# starterkit_v2.net
KiCad netlist of a schematic drawn in EAGLE
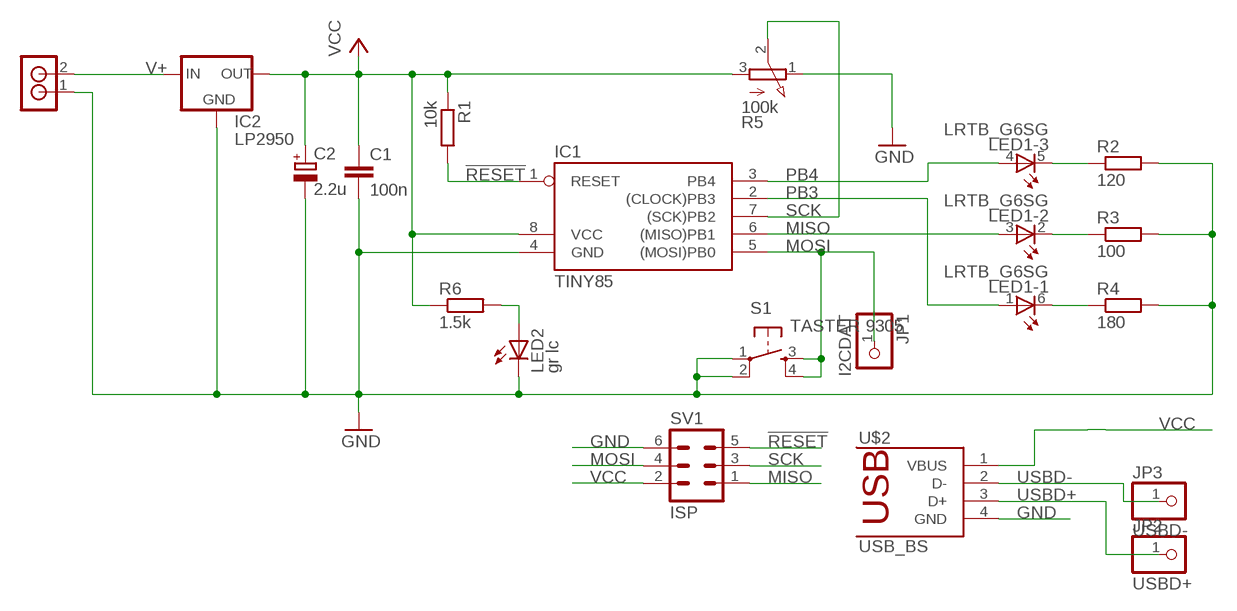
[diagram p0: schematic, sheet 1]

(export (version "E")
  (design (tool "Eeschema 10.0.6"))
  (components
    (comp (ref "C1")
      (value "100n")
      (footprint "eagle-import:C0805")
      (libsource (lib "eagle-import") (part "C-EUC0805"))
    )
    (comp (ref "C2")
      (value "2.2u")
      (footprint "eagle-import:E2-5")
      (libsource (lib "eagle-import") (part "CPOL-EUE2-5"))
    )
    (comp (ref "IC1")
      (value "TINY85")
      (footprint "eagle-import:DIL08")
      (libsource (lib "eagle-import") (part "TINY22P"))
    )
    (comp (ref "IC2")
      (value "LP2950")
      (footprint "eagle-import:TO92")
      (libsource (lib "eagle-import") (part "LP2950?ACZ-5.0"))
    )
    (comp (ref "JP1")
      (value "I2CDAT")
      (footprint "eagle-import:1X01")
      (libsource (lib "eagle-import") (part "PINHD-1X1"))
    )
    (comp (ref "JP2")
      (value "USBD+")
      (footprint "eagle-import:1X01")
      (libsource (lib "eagle-import") (part "PINHD-1X1"))
    )
    (comp (ref "JP3")
      (value "USBD-")
      (footprint "eagle-import:1X01")
      (libsource (lib "eagle-import") (part "PINHD-1X1"))
    )
    (comp (ref "LED1")
      (value "LRTB_G6SG")
      (footprint "eagle-import:LRTB_G6SG")
      (libsource (lib "eagle-import") (part "LRTB_G6SG"))
    )
    (comp (ref "LED2")
      (value "gr lc")
      (footprint "eagle-import:LED3MM")
      (libsource (lib "eagle-import") (part "LED3MM"))
    )
    (comp (ref "R1")
      (value "10k")
      (footprint "eagle-import:R0805")
      (libsource (lib "eagle-import") (part "R-EU_R0805"))
    )
    (comp (ref "R2")
      (value "120")
      (footprint "eagle-import:R0805")
      (libsource (lib "eagle-import") (part "R-EU_R0805"))
    )
    (comp (ref "R3")
      (value "100")
      (footprint "eagle-import:R0805")
      (libsource (lib "eagle-import") (part "R-EU_R0805"))
    )
    (comp (ref "R4")
      (value "180")
      (footprint "eagle-import:R0805")
      (libsource (lib "eagle-import") (part "R-EU_R0805"))
    )
    (comp (ref "R5")
      (value "100k")
      (footprint "eagle-import:ALPS_RK09K113")
      (libsource (lib "eagle-import") (part "ALPS_RK09K113"))
    )
    (comp (ref "R6")
      (value "1.5k")
      (footprint "eagle-import:R0805")
      (libsource (lib "eagle-import") (part "R-EU_R0805"))
    )
    (comp (ref "S1")
      (value "TASTER 9305")
      (footprint "eagle-import:JTP-1130")
      (libsource (lib "eagle-import") (part "JTP-1130C"))
    )
    (comp (ref "SV1")
      (value "ISP")
      (footprint "eagle-import:ML6")
      (libsource (lib "eagle-import") (part "ML6"))
    )
    (comp (ref "U$1")
      (value "RIACON_101_2")
      (footprint "eagle-import:RIACON_101_2")
      (libsource (lib "eagle-import") (part "RIACON_101_2"))
    )
    (comp (ref "U$2")
      (value "USB_BS")
      (footprint "eagle-import:USB_B_UP-S")
      (libsource (lib "eagle-import") (part "USB_BS"))
    )
  )
  (nets
    (net (code "1") (name "/MISO") (class "Default")
      (node (ref "IC1") (pin "6") (pinfunction "(MISO)PB1_6") (pintype "bidirectional"))
      (node (ref "LED1") (pin "3") (pinfunction "A_3") (pintype "passive"))
      (node (ref "SV1") (pin "1") (pinfunction "1_1") (pintype "passive"))
    )
    (net (code "2") (name "/MOSI") (class "Default")
      (node (ref "IC1") (pin "5") (pinfunction "(MOSI)PB0_5") (pintype "bidirectional"))
      (node (ref "JP1") (pin "1") (pinfunction "1_1") (pintype "passive"))
      (node (ref "S1") (pin "3") (pinfunction "S_3") (pintype "passive"))
      (node (ref "S1") (pin "4") (pinfunction "S1_4") (pintype "passive"))
      (node (ref "SV1") (pin "4") (pinfunction "4_4") (pintype "passive"))
    )
    (net (code "3") (name "/PB3") (class "Default")
      (node (ref "IC1") (pin "2") (pinfunction "(CLOCK)PB3_2") (pintype "bidirectional"))
      (node (ref "LED1") (pin "1") (pinfunction "A_1") (pintype "passive"))
    )
    (net (code "4") (name "/PB4") (class "Default")
      (node (ref "IC1") (pin "3") (pinfunction "PB4_3") (pintype "bidirectional"))
      (node (ref "LED1") (pin "4") (pinfunction "A_4") (pintype "passive"))
    )
    (net (code "5") (name "/SCK") (class "Default")
      (node (ref "IC1") (pin "7") (pinfunction "(SCK)PB2_7") (pintype "bidirectional"))
      (node (ref "R5") (pin "2") (pinfunction "S_2") (pintype "passive"))
      (node (ref "SV1") (pin "3") (pinfunction "3_3") (pintype "passive"))
    )
    (net (code "6") (name "/USBD+") (class "Default")
      (node (ref "JP2") (pin "1") (pinfunction "1_1") (pintype "passive"))
      (node (ref "U$2") (pin "3") (pinfunction "D+_3") (pintype "passive"))
    )
    (net (code "7") (name "/USBD-") (class "Default")
      (node (ref "JP3") (pin "1") (pinfunction "1_1") (pintype "passive"))
      (node (ref "U$2") (pin "2") (pinfunction "D-_2") (pintype "passive"))
    )
    (net (code "8") (name "/V+") (class "Default")
      (node (ref "IC2") (pin "3") (pinfunction "IN_3") (pintype "input"))
      (node (ref "U$1") (pin "2") (pinfunction "2_2") (pintype "passive"))
    )
    (net (code "9") (name "/~{RESET}") (class "Default")
      (node (ref "IC1") (pin "1") (pinfunction "RESET_1") (pintype "input"))
      (node (ref "R1") (pin "2") (pinfunction "2_2") (pintype "passive"))
      (node (ref "SV1") (pin "5") (pinfunction "5_5") (pintype "passive"))
    )
    (net (code "10") (name "GND") (class "Default")
      (node (ref "C1") (pin "2") (pinfunction "2_2") (pintype "passive"))
      (node (ref "C2") (pin "-") (pinfunction "-_-") (pintype "passive"))
      (node (ref "IC1") (pin "4") (pinfunction "GND_4") (pintype "power_in"))
      (node (ref "IC2") (pin "2") (pinfunction "GND_2") (pintype "input"))
      (node (ref "LED2") (pin "K") (pinfunction "C_K") (pintype "passive"))
      (node (ref "R2") (pin "2") (pinfunction "2_2") (pintype "passive"))
      (node (ref "R3") (pin "2") (pinfunction "2_2") (pintype "passive"))
      (node (ref "R4") (pin "2") (pinfunction "2_2") (pintype "passive"))
      (node (ref "R5") (pin "1") (pinfunction "E_1") (pintype "passive"))
      (node (ref "S1") (pin "1") (pinfunction "P_1") (pintype "passive"))
      (node (ref "S1") (pin "2") (pinfunction "P1_2") (pintype "passive"))
      (node (ref "SV1") (pin "6") (pinfunction "6_6") (pintype "passive"))
      (node (ref "U$1") (pin "1") (pinfunction "1_1") (pintype "passive"))
      (node (ref "U$2") (pin "4") (pinfunction "GND_4") (pintype "passive"))
    )
    (net (code "11") (name "Net-(LED1A-C)") (class "Default")
      (node (ref "LED1") (pin "6") (pinfunction "C_6") (pintype "passive"))
      (node (ref "R4") (pin "1") (pinfunction "1_1") (pintype "passive"))
    )
    (net (code "12") (name "Net-(LED1B-C)") (class "Default")
      (node (ref "LED1") (pin "2") (pinfunction "C_2") (pintype "passive"))
      (node (ref "R3") (pin "1") (pinfunction "1_1") (pintype "passive"))
    )
    (net (code "13") (name "Net-(LED1C-C)") (class "Default")
      (node (ref "LED1") (pin "5") (pinfunction "C_5") (pintype "passive"))
      (node (ref "R2") (pin "1") (pinfunction "1_1") (pintype "passive"))
    )
    (net (code "14") (name "Net-(LED2-PadA)") (class "Default")
      (node (ref "LED2") (pin "A") (pinfunction "A_A") (pintype "passive"))
      (node (ref "R6") (pin "2") (pinfunction "2_2") (pintype "passive"))
    )
    (net (code "15") (name "VCC") (class "Default")
      (node (ref "C1") (pin "1") (pinfunction "1_1") (pintype "passive"))
      (node (ref "C2") (pin "+") (pinfunction "+_+") (pintype "passive"))
      (node (ref "IC1") (pin "8") (pinfunction "VCC_8") (pintype "power_in"))
      (node (ref "IC2") (pin "1") (pinfunction "OUT_1") (pintype "passive"))
      (node (ref "R1") (pin "1") (pinfunction "1_1") (pintype "passive"))
      (node (ref "R5") (pin "3") (pinfunction "A_3") (pintype "passive"))
      (node (ref "R6") (pin "1") (pinfunction "1_1") (pintype "passive"))
      (node (ref "SV1") (pin "2") (pinfunction "2_2") (pintype "passive"))
      (node (ref "U$2") (pin "1") (pinfunction "VBUS_1") (pintype "passive"))
    )
  )
)
